# mother_card_13.net
KiCad netlist of a schematic drawn in EAGLE
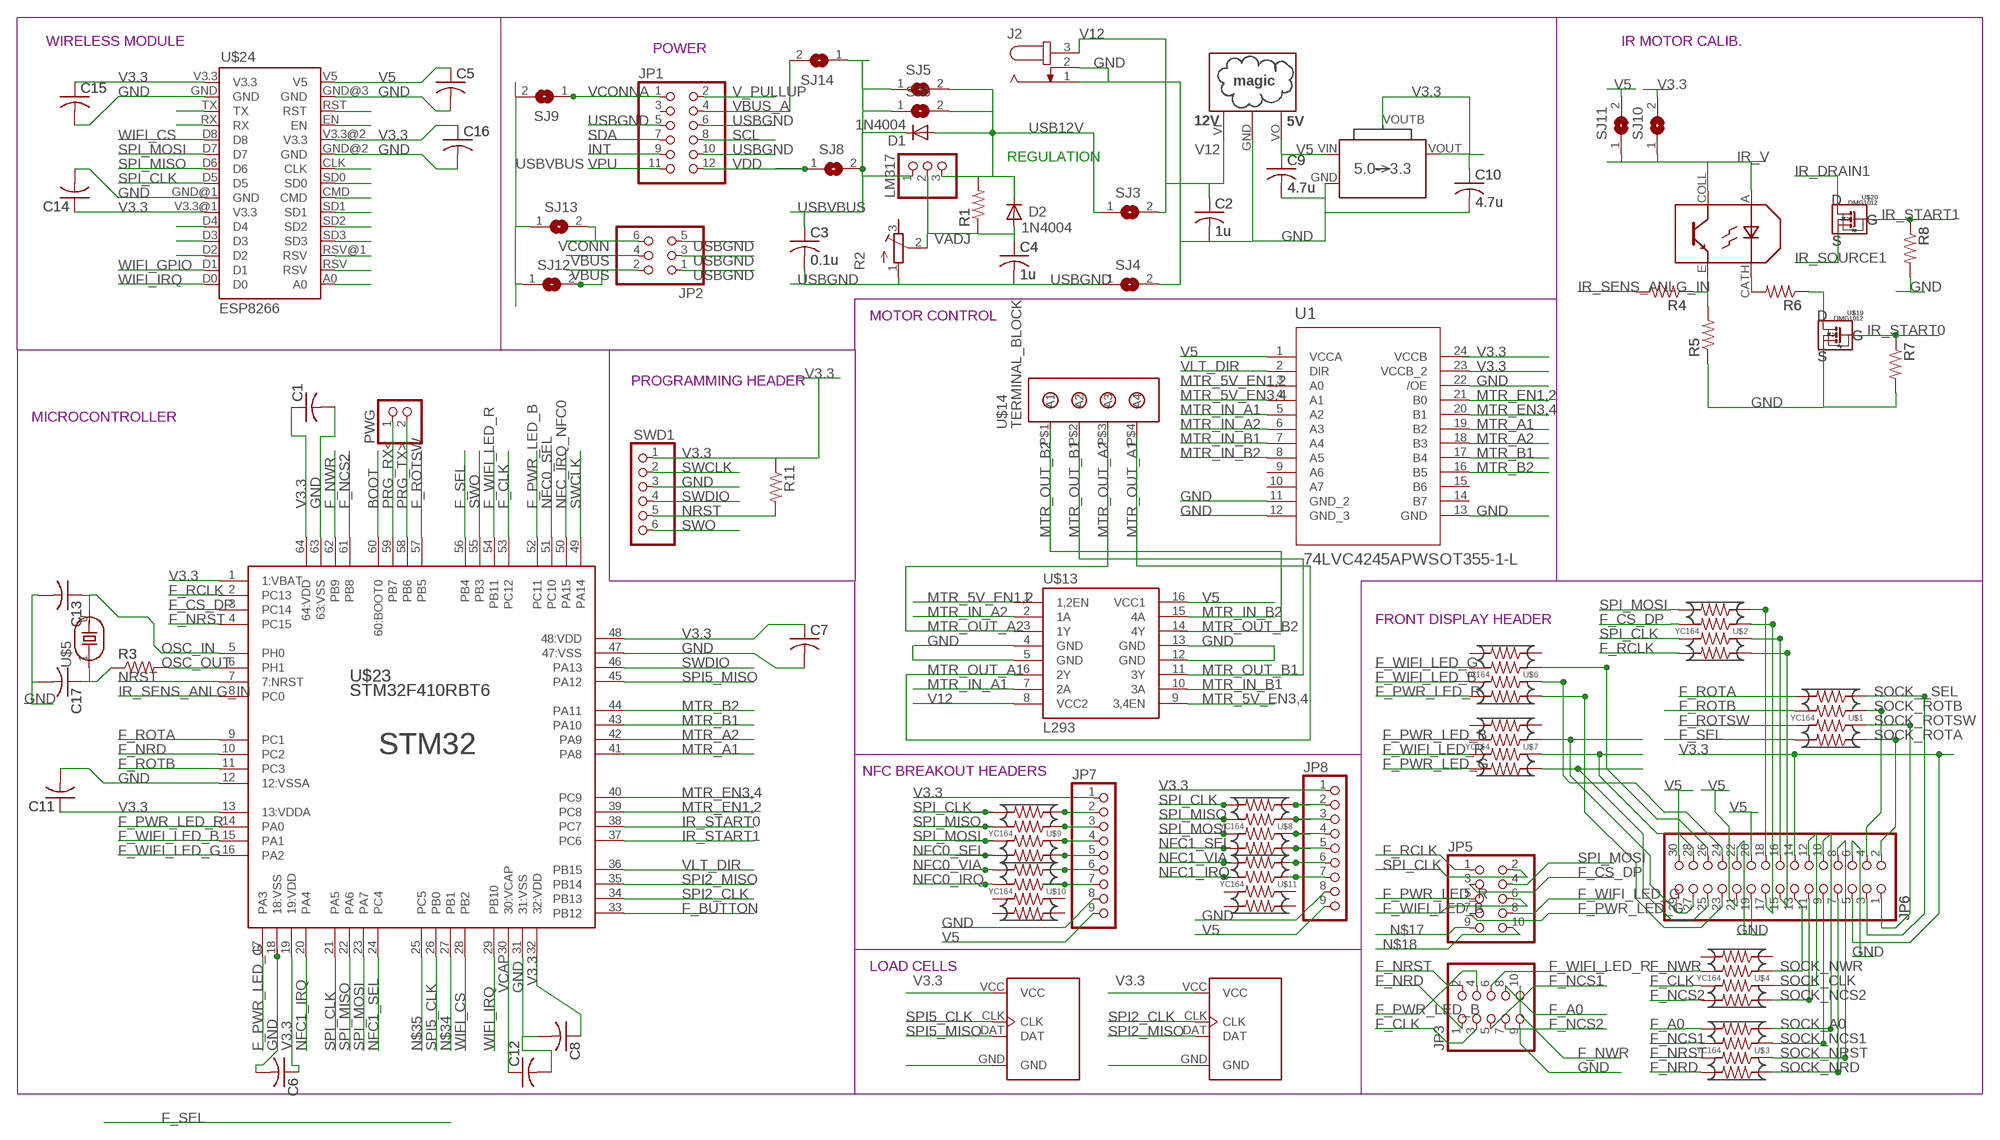
[diagram p0: schematic, sheet 1]

(export (version "E")
  (design (tool "Eeschema 10.0.6"))
  (components
    (comp (ref "C1")
      (value "C-USC0805")
      (footprint "eagle-import:C0805")
      (libsource (lib "eagle-import") (part "C-USC0805"))
    )
    (comp (ref "C2")
      (value "1u")
      (footprint "eagle-import:C0805")
      (libsource (lib "eagle-import") (part "C-USC0805"))
    )
    (comp (ref "C3")
      (value "0.1u")
      (footprint "eagle-import:C0805")
      (libsource (lib "eagle-import") (part "C-USC0805"))
    )
    (comp (ref "C4")
      (value "1u")
      (footprint "eagle-import:C0805")
      (libsource (lib "eagle-import") (part "C-USC0805"))
    )
    (comp (ref "C5")
      (value "C-USC0805")
      (footprint "eagle-import:C0805")
      (libsource (lib "eagle-import") (part "C-USC0805"))
    )
    (comp (ref "C6")
      (value "C-USC0805")
      (footprint "eagle-import:C0805")
      (libsource (lib "eagle-import") (part "C-USC0805"))
    )
    (comp (ref "C7")
      (value "C-USC0805")
      (footprint "eagle-import:C0805")
      (libsource (lib "eagle-import") (part "C-USC0805"))
    )
    (comp (ref "C8")
      (value "C-USC0805")
      (footprint "eagle-import:C0805")
      (libsource (lib "eagle-import") (part "C-USC0805"))
    )
    (comp (ref "C9")
      (value "4.7u")
      (footprint "eagle-import:C0805")
      (libsource (lib "eagle-import") (part "C-USC0805"))
    )
    (comp (ref "C10")
      (value "4.7u")
      (footprint "eagle-import:C0805")
      (libsource (lib "eagle-import") (part "C-USC0805"))
    )
    (comp (ref "C11")
      (value "C-USC0805")
      (footprint "eagle-import:C0805")
      (libsource (lib "eagle-import") (part "C-USC0805"))
    )
    (comp (ref "C12")
      (value "C-USC0805")
      (footprint "eagle-import:C0805")
      (libsource (lib "eagle-import") (part "C-USC0805"))
    )
    (comp (ref "C13")
      (value "C-USC0603")
      (footprint "eagle-import:C0603")
      (libsource (lib "eagle-import") (part "C-USC0603"))
    )
    (comp (ref "C14")
      (value "C-USC0805")
      (footprint "eagle-import:C0805")
      (libsource (lib "eagle-import") (part "C-USC0805"))
    )
    (comp (ref "C15")
      (value "C-USC0805")
      (footprint "eagle-import:C0805")
      (libsource (lib "eagle-import") (part "C-USC0805"))
    )
    (comp (ref "C16")
      (value "C-USC0805")
      (footprint "eagle-import:C0805")
      (libsource (lib "eagle-import") (part "C-USC0805"))
    )
    (comp (ref "C17")
      (value "C-USC0603")
      (footprint "eagle-import:C0603")
      (libsource (lib "eagle-import") (part "C-USC0603"))
    )
    (comp (ref "D1")
      (value "1N4004")
      (footprint "eagle-import:DO41-10")
      (libsource (lib "eagle-import") (part "1N4004"))
    )
    (comp (ref "D2")
      (value "1N4004")
      (footprint "eagle-import:DO41-10")
      (libsource (lib "eagle-import") (part "1N4004"))
    )
    (comp (ref "J2")
      (value "JACK-PLUG0")
      (footprint "eagle-import:SPC4077")
      (libsource (lib "eagle-import") (part "JACK-PLUG0"))
    )
    (comp (ref "JP1")
      (value "PINHD-2X6")
      (footprint "eagle-import:2X06")
      (libsource (lib "eagle-import") (part "PINHD-2X6"))
    )
    (comp (ref "JP2")
      (value "PINHD-2X3")
      (footprint "eagle-import:2X03")
      (libsource (lib "eagle-import") (part "PINHD-2X3"))
    )
    (comp (ref "JP3")
      (value "PINHD-2X5")
      (footprint "eagle-import:2X05")
      (libsource (lib "eagle-import") (part "PINHD-2X5"))
    )
    (comp (ref "JP5")
      (value "PINHD-2X5")
      (footprint "eagle-import:2X05")
      (libsource (lib "eagle-import") (part "PINHD-2X5"))
    )
    (comp (ref "JP6")
      (value "PINHD-2X15/SOCK")
      (footprint "eagle-import:2X15_SOCK")
      (libsource (lib "eagle-import") (part "PINHD-2X15/SOCK"))
    )
    (comp (ref "JP7")
      (value "PINHD-1X9/90")
      (footprint "eagle-import:1X09_90")
      (libsource (lib "eagle-import") (part "PINHD-1X9/90"))
    )
    (comp (ref "JP8")
      (value "PINHD-1X9/90")
      (footprint "eagle-import:1X09_90")
      (libsource (lib "eagle-import") (part "PINHD-1X9/90"))
    )
    (comp (ref "LM317")
      (value "PINHD-1X3")
      (footprint "eagle-import:1X03")
      (libsource (lib "eagle-import") (part "PINHD-1X3"))
    )
    (comp (ref "PWG")
      (value "PINHD-1X2")
      (footprint "eagle-import:1X02")
      (libsource (lib "eagle-import") (part "PINHD-1X2"))
    )
    (comp (ref "R1")
      (value "R-US_R0805")
      (footprint "eagle-import:R0805")
      (libsource (lib "eagle-import") (part "seniorDesign_R-US_R0805"))
    )
    (comp (ref "R2")
      (value "R-TRIMM64W")
      (footprint "eagle-import:RTRIM64W")
      (libsource (lib "eagle-import") (part "R-TRIMM64W"))
    )
    (comp (ref "R3")
      (value "R-US_R0805")
      (footprint "eagle-import:R0805")
      (libsource (lib "eagle-import") (part "seniorDesign_R-US_R0805"))
    )
    (comp (ref "R4")
      (value "R-US_R0805")
      (footprint "eagle-import:R0805")
      (libsource (lib "eagle-import") (part "seniorDesign_R-US_R0805"))
    )
    (comp (ref "R5")
      (value "R-US_R0805")
      (footprint "eagle-import:R0805")
      (libsource (lib "eagle-import") (part "seniorDesign_R-US_R0805"))
    )
    (comp (ref "R6")
      (value "R-US_R0805")
      (footprint "eagle-import:R0805")
      (libsource (lib "eagle-import") (part "seniorDesign_R-US_R0805"))
    )
    (comp (ref "R7")
      (value "R-US_R0805")
      (footprint "eagle-import:R0805")
      (libsource (lib "eagle-import") (part "seniorDesign_R-US_R0805"))
    )
    (comp (ref "R8")
      (value "R-US_R0805")
      (footprint "eagle-import:R0805")
      (libsource (lib "eagle-import") (part "seniorDesign_R-US_R0805"))
    )
    (comp (ref "R11")
      (value "R-US_R0805")
      (footprint "eagle-import:R0805")
      (libsource (lib "eagle-import") (part "R-US_R0805"))
    )
    (comp (ref "SJ3") (value "SJ") (footprint "eagle-import:SJ") (libsource (lib "eagle-import") (part "SJ")))
    (comp (ref "SJ4") (value "SJ") (footprint "eagle-import:SJ") (libsource (lib "eagle-import") (part "SJ")))
    (comp (ref "SJ5") (value "SJ") (footprint "eagle-import:SJ") (libsource (lib "eagle-import") (part "SJ")))
    (comp (ref "SJ6") (value "SJ") (footprint "eagle-import:SJ") (libsource (lib "eagle-import") (part "SJ")))
    (comp (ref "SJ8") (value "SJ") (footprint "eagle-import:SJ") (libsource (lib "eagle-import") (part "SJ")))
    (comp (ref "SJ9") (value "SJ") (footprint "eagle-import:SJ") (libsource (lib "eagle-import") (part "SJ")))
    (comp (ref "SJ10")
      (value "SJ")
      (footprint "eagle-import:SJ")
      (libsource (lib "eagle-import") (part "SJ"))
    )
    (comp (ref "SJ11")
      (value "SJ")
      (footprint "eagle-import:SJ")
      (libsource (lib "eagle-import") (part "SJ"))
    )
    (comp (ref "SJ12")
      (value "SJ")
      (footprint "eagle-import:SJ")
      (libsource (lib "eagle-import") (part "SJ"))
    )
    (comp (ref "SJ13")
      (value "SJ")
      (footprint "eagle-import:SJ")
      (libsource (lib "eagle-import") (part "SJ"))
    )
    (comp (ref "SJ14")
      (value "SJ")
      (footprint "eagle-import:SJ")
      (libsource (lib "eagle-import") (part "SJ"))
    )
    (comp (ref "SWD1")
      (value "PINHD-1X6")
      (footprint "eagle-import:1X06")
      (libsource (lib "eagle-import") (part "PINHD-1X6"))
    )
    (comp (ref "U$1")
      (value "YC164")
      (footprint "eagle-import:YC164")
      (libsource (lib "eagle-import") (part "YC164"))
    )
    (comp (ref "U$2")
      (value "YC164")
      (footprint "eagle-import:YC164")
      (libsource (lib "eagle-import") (part "YC164"))
    )
    (comp (ref "U$3")
      (value "YC164")
      (footprint "eagle-import:YC164")
      (libsource (lib "eagle-import") (part "YC164"))
    )
    (comp (ref "U$4")
      (value "YC164")
      (footprint "eagle-import:YC164")
      (libsource (lib "eagle-import") (part "YC164"))
    )
    (comp (ref "U$5")
      (value "HC-49S_9B")
      (footprint "eagle-import:HC-49S_9B")
      (libsource (lib "eagle-import") (part "HC-49S_9B"))
    )
    (comp (ref "U$6")
      (value "YC164")
      (footprint "eagle-import:YC164")
      (libsource (lib "eagle-import") (part "YC164"))
    )
    (comp (ref "U$7")
      (value "YC164")
      (footprint "eagle-import:YC164")
      (libsource (lib "eagle-import") (part "YC164"))
    )
    (comp (ref "U$8")
      (value "YC164")
      (footprint "eagle-import:YC164")
      (libsource (lib "eagle-import") (part "YC164"))
    )
    (comp (ref "U$9")
      (value "YC164")
      (footprint "eagle-import:YC164")
      (libsource (lib "eagle-import") (part "YC164"))
    )
    (comp (ref "U$10")
      (value "YC164")
      (footprint "eagle-import:YC164")
      (libsource (lib "eagle-import") (part "YC164"))
    )
    (comp (ref "U$11")
      (value "YC164")
      (footprint "eagle-import:YC164")
      (libsource (lib "eagle-import") (part "YC164"))
    )
    (comp (ref "U$13")
      (value "L293")
      (footprint "eagle-import:DIL16")
      (libsource (lib "eagle-import") (part "L293"))
    )
    (comp (ref "U$14")
      (value "TERMINAL_BLOCK")
      (footprint "eagle-import:1X4_BLOCK")
      (libsource (lib "eagle-import") (part "TERMINAL_BLOCK"))
    )
    (comp (ref "U$15")
      (value "AP2114H")
      (footprint "eagle-import:AP2114H")
      (libsource (lib "eagle-import") (part "AP2114H"))
    )
    (comp (ref "U$16")
      (value "OKI-78SR-W36")
      (footprint "eagle-import:SIP3")
      (libsource (lib "eagle-import") (part "OKI-78SR-W36"))
    )
    (comp (ref "U$18")
      (value "TCRT5000")
      (footprint "eagle-import:TCRT5000")
      (libsource (lib "eagle-import") (part "TCRT5000"))
    )
    (comp (ref "U$19")
      (value "DMG1012")
      (footprint "eagle-import:SOT323")
      (libsource (lib "eagle-import") (part "DMG1012"))
    )
    (comp (ref "U$20")
      (value "DMG1012")
      (footprint "eagle-import:SOT323")
      (libsource (lib "eagle-import") (part "DMG1012"))
    )
    (comp (ref "U$21")
      (value "HX711")
      (footprint "eagle-import:HX711")
      (libsource (lib "eagle-import") (part "HX711"))
    )
    (comp (ref "U$22")
      (value "HX711")
      (footprint "eagle-import:HX711")
      (libsource (lib "eagle-import") (part "HX711"))
    )
    (comp (ref "U$23")
      (value "STM32F410RBT6")
      (footprint "eagle-import:QFP50P1200X1200X160-64N")
      (libsource (lib "eagle-import") (part "STM32F410RBT6"))
    )
    (comp (ref "U$24")
      (value "ESP8266")
      (footprint "eagle-import:ESP8266")
      (libsource (lib "eagle-import") (part "ESP8266"))
    )
    (comp (ref "U1")
      (value "74LVC4245APWSOT355-1-L")
      (footprint "eagle-import:SOT355-1-L")
      (fields (field (name "MANUFACTURER_PART_NUMBER") "74LVC4245APW"))
      (libsource (lib "eagle-import") (part "74LVC4245APWSOT355-1-L"))
    )
  )
  (nets
    (net (code "1") (name "/BOOT") (class "Default")
      (node (ref "U$23") (pin "60") (pinfunction "60:BOOT0_60") (pintype "bidirectional"))
    )
    (net (code "2") (name "/F_A0") (class "Default")
      (node (ref "JP3") (pin "8") (pinfunction "8_8") (pintype "passive"))
      (node (ref "U$3") (pin "P$4") (pinfunction "4_P$4") (pintype "passive"))
    )
    (net (code "3") (name "/F_BUTTON") (class "Default")
      (node (ref "U$23") (pin "33") (pinfunction "PB12_33") (pintype "bidirectional"))
    )
    (net (code "4") (name "/F_CLK") (class "Default")
      (node (ref "JP3") (pin "3") (pinfunction "3_3") (pintype "passive"))
      (node (ref "U$23") (pin "53") (pinfunction "PC12_53") (pintype "bidirectional"))
      (node (ref "U$4") (pin "P$2") (pinfunction "2_P$2") (pintype "passive"))
    )
    (net (code "5") (name "/F_CS_DP") (class "Default")
      (node (ref "JP5") (pin "3") (pinfunction "3_3") (pintype "passive"))
      (node (ref "U$2") (pin "P$3") (pinfunction "3_P$3") (pintype "passive"))
      (node (ref "U$23") (pin "3") (pinfunction "PC14_3") (pintype "bidirectional"))
    )
    (net (code "6") (name "/F_NCS1") (class "Default")
      (node (ref "JP3") (pin "5") (pinfunction "5_5") (pintype "passive"))
      (node (ref "U$3") (pin "P$3") (pinfunction "3_P$3") (pintype "passive"))
    )
    (net (code "7") (name "/F_NCS2") (class "Default")
      (node (ref "JP3") (pin "7") (pinfunction "7_7") (pintype "passive"))
      (node (ref "U$23") (pin "61") (pinfunction "PB8_61") (pintype "bidirectional"))
      (node (ref "U$4") (pin "P$1") (pinfunction "1_P$1") (pintype "passive"))
    )
    (net (code "8") (name "/F_NRD") (class "Default")
      (node (ref "JP3") (pin "1") (pinfunction "1_1") (pintype "passive"))
      (node (ref "U$23") (pin "10") (pinfunction "PC2_10") (pintype "bidirectional"))
      (node (ref "U$3") (pin "P$1") (pinfunction "1_P$1") (pintype "passive"))
    )
    (net (code "9") (name "/F_NRST") (class "Default")
      (node (ref "JP3") (pin "2") (pinfunction "2_2") (pintype "passive"))
      (node (ref "U$23") (pin "4") (pinfunction "PC15_4") (pintype "bidirectional"))
      (node (ref "U$3") (pin "P$2") (pinfunction "2_P$2") (pintype "passive"))
    )
    (net (code "10") (name "/F_NWR") (class "Default")
      (node (ref "JP3") (pin "10") (pinfunction "10_10") (pintype "passive"))
      (node (ref "U$23") (pin "62") (pinfunction "PB9_62") (pintype "bidirectional"))
      (node (ref "U$4") (pin "P$3") (pinfunction "3_P$3") (pintype "passive"))
    )
    (net (code "11") (name "/F_PWR_LED_B") (class "Default")
      (node (ref "JP3") (pin "4") (pinfunction "4_4") (pintype "passive"))
      (node (ref "U$23") (pin "52") (pinfunction "PC11_52") (pintype "bidirectional"))
      (node (ref "U$7") (pin "P$3") (pinfunction "3_P$3") (pintype "passive"))
    )
    (net (code "12") (name "/F_PWR_LED_G") (class "Default")
      (node (ref "JP5") (pin "7") (pinfunction "7_7") (pintype "passive"))
      (node (ref "U$23") (pin "17") (pinfunction "PA3_17") (pintype "bidirectional"))
      (node (ref "U$7") (pin "P$1") (pinfunction "1_P$1") (pintype "passive"))
    )
    (net (code "13") (name "/F_PWR_LED_R") (class "Default")
      (node (ref "JP5") (pin "5") (pinfunction "5_5") (pintype "passive"))
      (node (ref "U$23") (pin "14") (pinfunction "PA0_14") (pintype "bidirectional"))
      (node (ref "U$6") (pin "P$1") (pinfunction "1_P$1") (pintype "passive"))
    )
    (net (code "14") (name "/F_RCLK") (class "Default")
      (node (ref "JP5") (pin "1") (pinfunction "1_1") (pintype "passive"))
      (node (ref "U$2") (pin "P$1") (pinfunction "1_P$1") (pintype "passive"))
      (node (ref "U$23") (pin "2") (pinfunction "PC13_2") (pintype "bidirectional"))
    )
    (net (code "15") (name "/F_ROTA") (class "Default")
      (node (ref "U$1") (pin "P$4") (pinfunction "4_P$4") (pintype "passive"))
      (node (ref "U$23") (pin "9") (pinfunction "PC1_9") (pintype "bidirectional"))
    )
    (net (code "16") (name "/F_ROTB") (class "Default")
      (node (ref "U$1") (pin "P$3") (pinfunction "3_P$3") (pintype "passive"))
      (node (ref "U$23") (pin "11") (pinfunction "PC3_11") (pintype "bidirectional"))
    )
    (net (code "17") (name "/F_ROTSW") (class "Default")
      (node (ref "U$1") (pin "P$2") (pinfunction "2_P$2") (pintype "passive"))
      (node (ref "U$23") (pin "57") (pinfunction "PB5_57") (pintype "bidirectional"))
    )
    (net (code "18") (name "/F_SEL") (class "Default")
      (node (ref "U$1") (pin "P$1") (pinfunction "1_P$1") (pintype "passive"))
      (node (ref "U$23") (pin "56") (pinfunction "PB4_56") (pintype "bidirectional"))
    )
    (net (code "19") (name "/F_WIFI_LED_B") (class "Default")
      (node (ref "JP5") (pin "6") (pinfunction "6_6") (pintype "passive"))
      (node (ref "U$23") (pin "15") (pinfunction "PA1_15") (pintype "bidirectional"))
      (node (ref "U$6") (pin "P$2") (pinfunction "2_P$2") (pintype "passive"))
    )
    (net (code "20") (name "/F_WIFI_LED_G") (class "Default")
      (node (ref "JP5") (pin "8") (pinfunction "8_8") (pintype "passive"))
      (node (ref "U$23") (pin "16") (pinfunction "PA2_16") (pintype "bidirectional"))
      (node (ref "U$6") (pin "P$3") (pinfunction "3_P$3") (pintype "passive"))
    )
    (net (code "21") (name "/F_WIFI_LED_R") (class "Default")
      (node (ref "JP3") (pin "6") (pinfunction "6_6") (pintype "passive"))
      (node (ref "U$23") (pin "54") (pinfunction "PB11_54") (pintype "bidirectional"))
      (node (ref "U$7") (pin "P$2") (pinfunction "2_P$2") (pintype "passive"))
    )
    (net (code "22") (name "/GND") (class "Default")
      (node (ref "C1") (pin "2") (pinfunction "2_2") (pintype "passive"))
      (node (ref "C10") (pin "2") (pinfunction "2_2") (pintype "passive"))
      (node (ref "C11") (pin "2") (pinfunction "2_2") (pintype "passive"))
      (node (ref "C12") (pin "2") (pinfunction "2_2") (pintype "passive"))
      (node (ref "C13") (pin "2") (pinfunction "2_2") (pintype "passive"))
      (node (ref "C14") (pin "2") (pinfunction "2_2") (pintype "passive"))
      (node (ref "C15") (pin "2") (pinfunction "2_2") (pintype "passive"))
      (node (ref "C16") (pin "2") (pinfunction "2_2") (pintype "passive"))
      (node (ref "C17") (pin "2") (pinfunction "2_2") (pintype "passive"))
      (node (ref "C2") (pin "2") (pinfunction "2_2") (pintype "passive"))
      (node (ref "C5") (pin "2") (pinfunction "2_2") (pintype "passive"))
      (node (ref "C6") (pin "2") (pinfunction "2_2") (pintype "passive"))
      (node (ref "C7") (pin "2") (pinfunction "2_2") (pintype "passive"))
      (node (ref "C8") (pin "2") (pinfunction "2_2") (pintype "passive"))
      (node (ref "C9") (pin "2") (pinfunction "2_2") (pintype "passive"))
      (node (ref "J2") (pin "1") (pinfunction "1_1") (pintype "passive"))
      (node (ref "J2") (pin "2") (pinfunction "2_2") (pintype "passive"))
      (node (ref "JP3") (pin "9") (pinfunction "9_9") (pintype "passive"))
      (node (ref "JP6") (pin "19") (pinfunction "19_19") (pintype "passive"))
      (node (ref "JP6") (pin "22") (pinfunction "22_22") (pintype "passive"))
      (node (ref "JP6") (pin "6") (pinfunction "6_6") (pintype "passive"))
      (node (ref "JP7") (pin "8") (pinfunction "8_8") (pintype "passive"))
      (node (ref "JP8") (pin "8") (pinfunction "8_8") (pintype "passive"))
      (node (ref "R5") (pin "1") (pinfunction "1_1") (pintype "passive"))
      (node (ref "R7") (pin "2") (pinfunction "2_2") (pintype "passive"))
      (node (ref "R8") (pin "2") (pinfunction "2_2") (pintype "passive"))
      (node (ref "SJ4") (pin "2") (pinfunction "2_2") (pintype "passive"))
      (node (ref "SWD1") (pin "3") (pinfunction "3_3") (pintype "passive"))
      (node (ref "U$13") (pin "12") (pinfunction "GND_12") (pintype "bidirectional"))
      (node (ref "U$13") (pin "13") (pinfunction "GND_13") (pintype "bidirectional"))
      (node (ref "U$13") (pin "4") (pinfunction "GND_4") (pintype "bidirectional"))
      (node (ref "U$13") (pin "5") (pinfunction "GND_5") (pintype "bidirectional"))
      (node (ref "U$15") (pin "GND") (pinfunction "GND_GND") (pintype "power_in"))
      (node (ref "U$16") (pin "GND") (pinfunction "P$2_GND") (pintype "power_in"))
      (node (ref "U$19") (pin "S") (pinfunction "S_S") (pintype "bidirectional"))
      (node (ref "U$21") (pin "GND") (pinfunction "GND_GND") (pintype "power_in"))
      (node (ref "U$22") (pin "GND") (pinfunction "GND_GND") (pintype "power_in"))
      (node (ref "U$23") (pin "12") (pinfunction "12:VSSA_12") (pintype "bidirectional"))
      (node (ref "U$23") (pin "18") (pinfunction "18:VSS_18") (pintype "bidirectional"))
      (node (ref "U$23") (pin "31") (pinfunction "31:VSS_31") (pintype "bidirectional"))
      (node (ref "U$23") (pin "47") (pinfunction "47:VSS_47") (pintype "bidirectional"))
      (node (ref "U$23") (pin "63") (pinfunction "63:VSS_63") (pintype "bidirectional"))
      (node (ref "U$24") (pin "GND") (pinfunction "GND_GND") (pintype "bidirectional"))
      (node (ref "U$24") (pin "GND@1") (pinfunction "GND_GND@1") (pintype "bidirectional"))
      (node (ref "U$24") (pin "GND@2") (pinfunction "GND_GND@2") (pintype "bidirectional"))
      (node (ref "U$24") (pin "GND@3") (pinfunction "GND_GND@3") (pintype "bidirectional"))
      (node (ref "U1") (pin "11") (pinfunction "GND_2_11") (pintype "power_in"))
      (node (ref "U1") (pin "12") (pinfunction "GND_3_12") (pintype "power_in"))
      (node (ref "U1") (pin "13") (pinfunction "GND_13") (pintype "power_in"))
      (node (ref "U1") (pin "22") (pinfunction "/OE_22") (pintype "input"))
    )
    (net (code "23") (name "/INT") (class "Default")
      (node (ref "JP1") (pin "9") (pinfunction "9_9") (pintype "passive"))
    )
    (net (code "24") (name "/IR_DRAIN1") (class "Default")
      (node (ref "U$20") (pin "D") (pinfunction "D_D") (pintype "bidirectional"))
    )
    (net (code "25") (name "/IR_SENS_ANLG_IN") (class "Default")
      (node (ref "R4") (pin "2") (pinfunction "2_2") (pintype "passive"))
      (node (ref "U$23") (pin "8") (pinfunction "PC0_8") (pintype "bidirectional"))
    )
    (net (code "26") (name "/IR_SOURCE1") (class "Default")
      (node (ref "U$20") (pin "S") (pinfunction "S_S") (pintype "bidirectional"))
    )
    (net (code "27") (name "/IR_START0") (class "Default")
      (node (ref "R7") (pin "1") (pinfunction "1_1") (pintype "passive"))
      (node (ref "U$19") (pin "G") (pinfunction "G_G") (pintype "bidirectional"))
      (node (ref "U$23") (pin "38") (pinfunction "PC7_38") (pintype "bidirectional"))
    )
    (net (code "28") (name "/IR_START1") (class "Default")
      (node (ref "R8") (pin "1") (pinfunction "1_1") (pintype "passive"))
      (node (ref "U$20") (pin "G") (pinfunction "G_G") (pintype "bidirectional"))
      (node (ref "U$23") (pin "37") (pinfunction "PC6_37") (pintype "bidirectional"))
    )
    (net (code "29") (name "/IR_V") (class "Default")
      (node (ref "SJ10") (pin "1") (pinfunction "1_1") (pintype "passive"))
      (node (ref "SJ11") (pin "1") (pinfunction "1_1") (pintype "passive"))
      (node (ref "U$18") (pin "A") (pinfunction "A_A") (pintype "bidirectional"))
      (node (ref "U$18") (pin "COLL") (pinfunction "COLL_COLL") (pintype "bidirectional"))
    )
    (net (code "30") (name "/MTR_5V_EN1,2") (class "Default")
      (node (ref "U$13") (pin "1") (pinfunction "1,2EN_1") (pintype "bidirectional"))
      (node (ref "U1") (pin "3") (pinfunction "A0_3") (pintype "bidirectional"))
    )
    (net (code "31") (name "/MTR_5V_EN3,4") (class "Default")
      (node (ref "U$13") (pin "9") (pinfunction "3,4EN_9") (pintype "bidirectional"))
      (node (ref "U1") (pin "4") (pinfunction "A1_4") (pintype "bidirectional"))
    )
    (net (code "32") (name "/MTR_A1") (class "Default")
      (node (ref "U$23") (pin "41") (pinfunction "PA8_41") (pintype "bidirectional"))
      (node (ref "U1") (pin "19") (pinfunction "B2_19") (pintype "bidirectional"))
    )
    (net (code "33") (name "/MTR_A2") (class "Default")
      (node (ref "U$23") (pin "42") (pinfunction "PA9_42") (pintype "bidirectional"))
      (node (ref "U1") (pin "18") (pinfunction "B3_18") (pintype "bidirectional"))
    )
    (net (code "34") (name "/MTR_B1") (class "Default")
      (node (ref "U$23") (pin "43") (pinfunction "PA10_43") (pintype "bidirectional"))
      (node (ref "U1") (pin "17") (pinfunction "B4_17") (pintype "bidirectional"))
    )
    (net (code "35") (name "/MTR_B2") (class "Default")
      (node (ref "U$23") (pin "44") (pinfunction "PA11_44") (pintype "bidirectional"))
      (node (ref "U1") (pin "16") (pinfunction "B5_16") (pintype "bidirectional"))
    )
    (net (code "36") (name "/MTR_EN1,2") (class "Default")
      (node (ref "U$23") (pin "39") (pinfunction "PC8_39") (pintype "bidirectional"))
      (node (ref "U1") (pin "21") (pinfunction "B0_21") (pintype "bidirectional"))
    )
    (net (code "37") (name "/MTR_EN3,4") (class "Default")
      (node (ref "U$23") (pin "40") (pinfunction "PC9_40") (pintype "bidirectional"))
      (node (ref "U1") (pin "20") (pinfunction "B1_20") (pintype "bidirectional"))
    )
    (net (code "38") (name "/MTR_IN_A1") (class "Default")
      (node (ref "U$13") (pin "7") (pinfunction "2A_7") (pintype "bidirectional"))
      (node (ref "U1") (pin "5") (pinfunction "A2_5") (pintype "bidirectional"))
    )
    (net (code "39") (name "/MTR_IN_A2") (class "Default")
      (node (ref "U$13") (pin "2") (pinfunction "1A_2") (pintype "bidirectional"))
      (node (ref "U1") (pin "6") (pinfunction "A3_6") (pintype "bidirectional"))
    )
    (net (code "40") (name "/MTR_IN_B1") (class "Default")
      (node (ref "U$13") (pin "10") (pinfunction "3A_10") (pintype "bidirectional"))
      (node (ref "U1") (pin "7") (pinfunction "A4_7") (pintype "bidirectional"))
    )
    (net (code "41") (name "/MTR_IN_B2") (class "Default")
      (node (ref "U$13") (pin "15") (pinfunction "4A_15") (pintype "bidirectional"))
      (node (ref "U1") (pin "8") (pinfunction "A5_8") (pintype "bidirectional"))
    )
    (net (code "42") (name "/MTR_OUT_A1") (class "Default")
      (node (ref "U$13") (pin "6") (pinfunction "2Y_6") (pintype "bidirectional"))
      (node (ref "U$14") (pin "P$4") (pinfunction "A4_P$4") (pintype "bidirectional"))
    )
    (net (code "43") (name "/MTR_OUT_A2") (class "Default")
      (node (ref "U$13") (pin "3") (pinfunction "1Y_3") (pintype "bidirectional"))
      (node (ref "U$14") (pin "P$3") (pinfunction "A3_P$3") (pintype "bidirectional"))
    )
    (net (code "44") (name "/MTR_OUT_B1") (class "Default")
      (node (ref "U$13") (pin "11") (pinfunction "3Y_11") (pintype "bidirectional"))
      (node (ref "U$14") (pin "P$2") (pinfunction "A2_P$2") (pintype "bidirectional"))
    )
    (net (code "45") (name "/MTR_OUT_B2") (class "Default")
      (node (ref "U$13") (pin "14") (pinfunction "4Y_14") (pintype "bidirectional"))
      (node (ref "U$14") (pin "P$1") (pinfunction "A1_P$1") (pintype "bidirectional"))
    )
    (net (code "46") (name "/N$17") (class "Default")
      (node (ref "JP5") (pin "9") (pinfunction "9_9") (pintype "passive"))
    )
    (net (code "47") (name "/N$18") (class "Default")
      (node (ref "JP5") (pin "10") (pinfunction "10_10") (pintype "passive"))
    )
    (net (code "48") (name "/N$34") (class "Default")
      (node (ref "U$23") (pin "27") (pinfunction "PB1_27") (pintype "bidirectional"))
    )
    (net (code "49") (name "/N$35") (class "Default")
      (node (ref "U$23") (pin "25") (pinfunction "PC5_25") (pintype "bidirectional"))
    )
    (net (code "50") (name "/NFC0_IRQ") (class "Default")
      (node (ref "U$10") (pin "P$3") (pinfunction "3_P$3") (pintype "passive"))
    )
    (net (code "51") (name "/NFC0_SEL") (class "Default")
      (node (ref "U$23") (pin "51") (pinfunction "PC10_51") (pintype "bidirectional"))
      (node (ref "U$9") (pin "P$1") (pinfunction "1_P$1") (pintype "passive"))
    )
    (net (code "52") (name "/NFC0_VIA") (class "Default")
      (node (ref "U$10") (pin "P$4") (pinfunction "4_P$4") (pintype "passive"))
    )
    (net (code "53") (name "/NFC1_IRQ") (class "Default")
      (node (ref "U$11") (pin "P$3") (pinfunction "3_P$3") (pintype "passive"))
      (node (ref "U$23") (pin "20") (pinfunction "PA4_20") (pintype "bidirectional"))
    )
    (net (code "54") (name "/NFC1_SEL") (class "Default")
      (node (ref "U$23") (pin "24") (pinfunction "PC4_24") (pintype "bidirectional"))
      (node (ref "U$8") (pin "P$1") (pinfunction "1_P$1") (pintype "passive"))
    )
    (net (code "55") (name "/NFC1_VIA") (class "Default")
      (node (ref "U$11") (pin "P$4") (pinfunction "4_P$4") (pintype "passive"))
    )
    (net (code "56") (name "/NFC_IRQ_NFC0") (class "Default")
      (node (ref "U$23") (pin "50") (pinfunction "PA15_50") (pintype "bidirectional"))
    )
    (net (code "57") (name "/NRST") (class "Default")
      (node (ref "R11") (pin "2") (pinfunction "2_2") (pintype "passive"))
      (node (ref "SWD1") (pin "5") (pinfunction "5_5") (pintype "passive"))
      (node (ref "U$23") (pin "7") (pinfunction "7:NRST_7") (pintype "bidirectional"))
    )
    (net (code "58") (name "/OSC_IN") (class "Default")
      (node (ref "C13") (pin "1") (pinfunction "1_1") (pintype "passive"))
      (node (ref "U$23") (pin "5") (pinfunction "PH0_5") (pintype "bidirectional"))
      (node (ref "U$5") (pin "0") (pinfunction "P$1_0") (pintype "bidirectional"))
    )
    (net (code "59") (name "/OSC_OUT") (class "Default")
      (node (ref "C17") (pin "1") (pinfunction "1_1") (pintype "passive"))
      (node (ref "R3") (pin "1") (pinfunction "1_1") (pintype "passive"))
      (node (ref "U$5") (pin "1") (pinfunction "P$2_1") (pintype "bidirectional"))
    )
    (net (code "60") (name "/PRG_RX<") (class "Default")
      (node (ref "PWG") (pin "1") (pinfunction "1_1") (pintype "passive"))
      (node (ref "U$23") (pin "59") (pinfunction "PB7_59") (pintype "bidirectional"))
    )
    (net (code "61") (name "/PRG_TX>") (class "Default")
      (node (ref "PWG") (pin "2") (pinfunction "2_2") (pintype "passive"))
      (node (ref "U$23") (pin "58") (pinfunction "PB6_58") (pintype "bidirectional"))
    )
    (net (code "62") (name "/SCL") (class "Default")
      (node (ref "JP1") (pin "8") (pinfunction "8_8") (pintype "passive"))
    )
    (net (code "63") (name "/SDA") (class "Default")
      (node (ref "JP1") (pin "7") (pinfunction "7_7") (pintype "passive"))
    )
    (net (code "64") (name "/SOCK_A0") (class "Default")
      (node (ref "JP6") (pin "10") (pinfunction "10_10") (pintype "passive"))
      (node (ref "U$3") (pin "P$44") (pinfunction "44_P$44") (pintype "passive"))
    )
    (net (code "65") (name "/SOCK_CLK") (class "Default")
      (node (ref "JP6") (pin "12") (pinfunction "12_12") (pintype "passive"))
      (node (ref "U$4") (pin "P$22") (pinfunction "22_P$22") (pintype "passive"))
    )
    (net (code "66") (name "/SOCK_NCS1") (class "Default")
      (node (ref "JP6") (pin "9") (pinfunction "9_9") (pintype "passive"))
      (node (ref "U$3") (pin "P$33") (pinfunction "33_P$33") (pintype "passive"))
    )
    (net (code "67") (name "/SOCK_NCS2") (class "Default")
      (node (ref "JP6") (pin "11") (pinfunction "11_11") (pintype "passive"))
      (node (ref "U$4") (pin "P$11") (pinfunction "11_P$11") (pintype "passive"))
    )
    (net (code "68") (name "/SOCK_NRD") (class "Default")
      (node (ref "JP6") (pin "7") (pinfunction "7_7") (pintype "passive"))
      (node (ref "U$3") (pin "P$11") (pinfunction "11_P$11") (pintype "passive"))
    )
    (net (code "69") (name "/SOCK_NRST") (class "Default")
      (node (ref "JP6") (pin "8") (pinfunction "8_8") (pintype "passive"))
      (node (ref "U$3") (pin "P$22") (pinfunction "22_P$22") (pintype "passive"))
    )
    (net (code "70") (name "/SOCK_NWR") (class "Default")
      (node (ref "JP6") (pin "13") (pinfunction "13_13") (pintype "passive"))
      (node (ref "U$4") (pin "P$33") (pinfunction "33_P$33") (pintype "passive"))
    )
    (net (code "71") (name "/SOCK_ROTA") (class "Default")
      (node (ref "JP6") (pin "2") (pinfunction "2_2") (pintype "passive"))
      (node (ref "U$1") (pin "P$11") (pinfunction "11_P$11") (pintype "passive"))
    )
    (net (code "72") (name "/SOCK_ROTB") (class "Default")
      (node (ref "JP6") (pin "4") (pinfunction "4_4") (pintype "passive"))
      (node (ref "U$1") (pin "P$33") (pinfunction "33_P$33") (pintype "passive"))
    )
    (net (code "73") (name "/SOCK_ROTSW") (class "Default")
      (node (ref "JP6") (pin "1") (pinfunction "1_1") (pintype "passive"))
      (node (ref "U$1") (pin "P$22") (pinfunction "22_P$22") (pintype "passive"))
    )
    (net (code "74") (name "/SOCK__SEL") (class "Default")
      (node (ref "JP6") (pin "3") (pinfunction "3_3") (pintype "passive"))
      (node (ref "U$1") (pin "P$44") (pinfunction "44_P$44") (pintype "passive"))
    )
    (net (code "75") (name "/SPI2_CLK") (class "Default")
      (node (ref "U$22") (pin "CLK") (pinfunction "CLK_CLK") (pintype "bidirectional"))
      (node (ref "U$23") (pin "34") (pinfunction "PB13_34") (pintype "bidirectional"))
    )
    (net (code "76") (name "/SPI2_MISO") (class "Default")
      (node (ref "U$22") (pin "DAT") (pinfunction "DAT_DAT") (pintype "bidirectional"))
      (node (ref "U$23") (pin "35") (pinfunction "PB14_35") (pintype "bidirectional"))
    )
    (net (code "77") (name "/SPI5_CLK") (class "Default")
      (node (ref "U$21") (pin "CLK") (pinfunction "CLK_CLK") (pintype "bidirectional"))
      (node (ref "U$23") (pin "26") (pinfunction "PB0_26") (pintype "bidirectional"))
    )
    (net (code "78") (name "/SPI5_MISO") (class "Default")
      (node (ref "U$21") (pin "DAT") (pinfunction "DAT_DAT") (pintype "bidirectional"))
      (node (ref "U$23") (pin "45") (pinfunction "PA12_45") (pintype "bidirectional"))
    )
    (net (code "79") (name "/SPI_CLK") (class "Default")
      (node (ref "JP5") (pin "2") (pinfunction "2_2") (pintype "passive"))
      (node (ref "U$2") (pin "P$2") (pinfunction "2_P$2") (pintype "passive"))
      (node (ref "U$23") (pin "21") (pinfunction "PA5_21") (pintype "bidirectional"))
      (node (ref "U$24") (pin "D5") (pinfunction "D5_D5") (pintype "bidirectional"))
      (node (ref "U$8") (pin "P$4") (pinfunction "4_P$4") (pintype "passive"))
      (node (ref "U$9") (pin "P$4") (pinfunction "4_P$4") (pintype "passive"))
    )
    (net (code "80") (name "/SPI_MISO") (class "Default")
      (node (ref "U$23") (pin "22") (pinfunction "PA6_22") (pintype "bidirectional"))
      (node (ref "U$24") (pin "D6") (pinfunction "D6_D6") (pintype "bidirectional"))
      (node (ref "U$8") (pin "P$3") (pinfunction "3_P$3") (pintype "passive"))
      (node (ref "U$9") (pin "P$3") (pinfunction "3_P$3") (pintype "passive"))
    )
    (net (code "81") (name "/SPI_MOSI") (class "Default")
      (node (ref "JP5") (pin "4") (pinfunction "4_4") (pintype "passive"))
      (node (ref "U$2") (pin "P$4") (pinfunction "4_P$4") (pintype "passive"))
      (node (ref "U$23") (pin "23") (pinfunction "PA7_23") (pintype "bidirectional"))
      (node (ref "U$24") (pin "D7") (pinfunction "D7_D7") (pintype "bidirectional"))
      (node (ref "U$8") (pin "P$2") (pinfunction "2_P$2") (pintype "passive"))
      (node (ref "U$9") (pin "P$2") (pinfunction "2_P$2") (pintype "passive"))
    )
    (net (code "82") (name "/SWCLK") (class "Default")
      (node (ref "SWD1") (pin "2") (pinfunction "2_2") (pintype "passive"))
      (node (ref "U$23") (pin "49") (pinfunction "PA14_49") (pintype "bidirectional"))
    )
    (net (code "83") (name "/SWDIO") (class "Default")
      (node (ref "SWD1") (pin "4") (pinfunction "4_4") (pintype "passive"))
      (node (ref "U$23") (pin "46") (pinfunction "PA13_46") (pintype "bidirectional"))
    )
    (net (code "84") (name "/SWO") (class "Default")
      (node (ref "SWD1") (pin "6") (pinfunction "6_6") (pintype "passive"))
      (node (ref "U$23") (pin "55") (pinfunction "PB3_55") (pintype "bidirectional"))
    )
    (net (code "85") (name "/USB12V") (class "Default")
      (node (ref "D1") (pin "A") (pinfunction "A_A") (pintype "passive"))
      (node (ref "D2") (pin "C") (pinfunction "C_C") (pintype "passive"))
      (node (ref "LM317") (pin "3") (pinfunction "3_3") (pintype "passive"))
      (node (ref "R1") (pin "2") (pinfunction "2_2") (pintype "passive"))
      (node (ref "SJ3") (pin "1") (pinfunction "1_1") (pintype "passive"))
      (node (ref "SJ5") (pin "2") (pinfunction "2_2") (pintype "passive"))
      (node (ref "SJ6") (pin "2") (pinfunction "2_2") (pintype "passive"))
    )
    (net (code "86") (name "/USBGND") (class "Default")
      (node (ref "C3") (pin "2") (pinfunction "2_2") (pintype "passive"))
      (node (ref "C4") (pin "2") (pinfunction "2_2") (pintype "passive"))
      (node (ref "JP1") (pin "10") (pinfunction "10_10") (pintype "passive"))
      (node (ref "JP1") (pin "5") (pinfunction "5_5") (pintype "passive"))
      (node (ref "JP1") (pin "6") (pinfunction "6_6") (pintype "passive"))
      (node (ref "JP2") (pin "1") (pinfunction "1_1") (pintype "passive"))
      (node (ref "JP2") (pin "3") (pinfunction "3_3") (pintype "passive"))
      (node (ref "JP2") (pin "5") (pinfunction "5_5") (pintype "passive"))
      (node (ref "R2") (pin "1") (pinfunction "A_1") (pintype "passive"))
      (node (ref "SJ4") (pin "1") (pinfunction "1_1") (pintype "passive"))
    )
    (net (code "87") (name "/USBVBUS") (class "Default")
      (node (ref "C3") (pin "1") (pinfunction "1_1") (pintype "passive"))
      (node (ref "D1") (pin "C") (pinfunction "C_C") (pintype "passive"))
      (node (ref "LM317") (pin "1") (pinfunction "1_1") (pintype "passive"))
      (node (ref "SJ12") (pin "1") (pinfunction "1_1") (pintype "passive"))
      (node (ref "SJ13") (pin "1") (pinfunction "1_1") (pintype "passive"))
      (node (ref "SJ14") (pin "1") (pinfunction "1_1") (pintype "passive"))
      (node (ref "SJ5") (pin "1") (pinfunction "1_1") (pintype "passive"))
      (node (ref "SJ6") (pin "1") (pinfunction "1_1") (pintype "passive"))
      (node (ref "SJ8") (pin "2") (pinfunction "2_2") (pintype "passive"))
      (node (ref "SJ9") (pin "2") (pinfunction "2_2") (pintype "passive"))
    )
    (net (code "88") (name "/V3.3") (class "Default")
      (node (ref "C1") (pin "1") (pinfunction "1_1") (pintype "passive"))
      (node (ref "C10") (pin "1") (pinfunction "1_1") (pintype "passive"))
      (node (ref "C11") (pin "1") (pinfunction "1_1") (pintype "passive"))
      (node (ref "C14") (pin "1") (pinfunction "1_1") (pintype "passive"))
      (node (ref "C15") (pin "1") (pinfunction "1_1") (pintype "passive"))
      (node (ref "C16") (pin "1") (pinfunction "1_1") (pintype "passive"))
      (node (ref "C6") (pin "1") (pinfunction "1_1") (pintype "passive"))
      (node (ref "C7") (pin "1") (pinfunction "1_1") (pintype "passive"))
      (node (ref "C8") (pin "1") (pinfunction "1_1") (pintype "passive"))
      (node (ref "JP6") (pin "14") (pinfunction "14_14") (pintype "passive"))
      (node (ref "JP6") (pin "5") (pinfunction "5_5") (pintype "passive"))
      (node (ref "JP7") (pin "1") (pinfunction "1_1") (pintype "passive"))
      (node (ref "JP8") (pin "1") (pinfunction "1_1") (pintype "passive"))
      (node (ref "R11") (pin "1") (pinfunction "1_1") (pintype "passive"))
      (node (ref "SJ10") (pin "2") (pinfunction "2_2") (pintype "passive"))
      (node (ref "SWD1") (pin "1") (pinfunction "1_1") (pintype "passive"))
      (node (ref "U$15") (pin "VOUT") (pinfunction "VO_VOUT") (pintype "output"))
      (node (ref "U$15") (pin "VOUTB") (pinfunction "BODY_VOUTB") (pintype "open_collector"))
      (node (ref "U$21") (pin "VCC") (pinfunction "VCC_VCC") (pintype "power_in"))
      (node (ref "U$22") (pin "VCC") (pinfunction "VCC_VCC") (pintype "power_in"))
      (node (ref "U$23") (pin "1") (pinfunction "1:VBAT_1") (pintype "bidirectional"))
      (node (ref "U$23") (pin "13") (pinfunction "13:VDDA_13") (pintype "bidirectional"))
      (node (ref "U$23") (pin "19") (pinfunction "19:VDD_19") (pintype "bidirectional"))
      (node (ref "U$23") (pin "32") (pinfunction "32:VDD_32") (pintype "bidirectional"))
      (node (ref "U$23") (pin "48") (pinfunction "48:VDD_48") (pintype "bidirectional"))
      (node (ref "U$23") (pin "64") (pinfunction "64:VDD_64") (pintype "bidirectional"))
      (node (ref "U$24") (pin "V3.3") (pinfunction "V3.3_V3.3") (pintype "bidirectional"))
      (node (ref "U$24") (pin "V3.3@1") (pinfunction "V3.3_V3.3@1") (pintype "bidirectional"))
      (node (ref "U$24") (pin "V3.3@2") (pinfunction "V3.3_V3.3@2") (pintype "bidirectional"))
      (node (ref "U1") (pin "23") (pinfunction "VCCB_2_23") (pintype "power_in"))
      (node (ref "U1") (pin "24") (pinfunction "VCCB_24") (pintype "power_in"))
    )
    (net (code "89") (name "/V5") (class "Default")
      (node (ref "C5") (pin "1") (pinfunction "1_1") (pintype "passive"))
      (node (ref "C9") (pin "1") (pinfunction "1_1") (pintype "passive"))
      (node (ref "JP6") (pin "20") (pinfunction "20_20") (pintype "passive"))
      (node (ref "JP6") (pin "21") (pinfunction "21_21") (pintype "passive"))
      (node (ref "JP6") (pin "30") (pinfunction "30_30") (pintype "passive"))
      (node (ref "JP7") (pin "9") (pinfunction "9_9") (pintype "passive"))
      (node (ref "JP8") (pin "9") (pinfunction "9_9") (pintype "passive"))
      (node (ref "SJ11") (pin "2") (pinfunction "2_2") (pintype "passive"))
      (node (ref "U$13") (pin "16") (pinfunction "VCC1_16") (pintype "bidirectional"))
      (node (ref "U$15") (pin "VIN") (pinfunction "VI_VIN") (pintype "input"))
      (node (ref "U$16") (pin "VO") (pinfunction "P$3_VO") (pintype "output"))
      (node (ref "U$24") (pin "V5") (pinfunction "V5_V5") (pintype "bidirectional"))
      (node (ref "U1") (pin "1") (pinfunction "VCCA_1") (pintype "power_in"))
    )
    (net (code "90") (name "/V12") (class "Default")
      (node (ref "C2") (pin "1") (pinfunction "1_1") (pintype "passive"))
      (node (ref "J2") (pin "3") (pinfunction "3_3") (pintype "passive"))
      (node (ref "SJ3") (pin "2") (pinfunction "2_2") (pintype "passive"))
      (node (ref "U$13") (pin "8") (pinfunction "VCC2_8") (pintype "bidirectional"))
      (node (ref "U$16") (pin "VI") (pinfunction "P$1_VI") (pintype "input"))
    )
    (net (code "91") (name "/VADJ") (class "Default")
      (node (ref "C4") (pin "1") (pinfunction "1_1") (pintype "passive"))
      (node (ref "D2") (pin "A") (pinfunction "A_A") (pintype "passive"))
      (node (ref "LM317") (pin "2") (pinfunction "2_2") (pintype "passive"))
      (node (ref "R1") (pin "1") (pinfunction "1_1") (pintype "passive"))
      (node (ref "R2") (pin "2") (pinfunction "S_2") (pintype "passive"))
    )
    (net (code "92") (name "/VBUS") (class "Default")
      (node (ref "JP2") (pin "2") (pinfunction "2_2") (pintype "passive"))
      (node (ref "JP2") (pin "4") (pinfunction "4_4") (pintype "passive"))
      (node (ref "SJ12") (pin "2") (pinfunction "2_2") (pintype "passive"))
    )
    (net (code "93") (name "/VBUS_A") (class "Default")
      (node (ref "JP1") (pin "4") (pinfunction "4_4") (pintype "passive"))
      (node (ref "SJ14") (pin "2") (pinfunction "2_2") (pintype "passive"))
    )
    (net (code "94") (name "/VCAP") (class "Default")
      (node (ref "C12") (pin "1") (pinfunction "1_1") (pintype "passive"))
      (node (ref "U$23") (pin "30") (pinfunction "30:VCAP_30") (pintype "bidirectional"))
    )
    (net (code "95") (name "/VCONN") (class "Default")
      (node (ref "JP2") (pin "6") (pinfunction "6_6") (pintype "passive"))
      (node (ref "SJ13") (pin "2") (pinfunction "2_2") (pintype "passive"))
    )
    (net (code "96") (name "/VCONNA") (class "Default")
      (node (ref "JP1") (pin "1") (pinfunction "1_1") (pintype "passive"))
      (node (ref "SJ9") (pin "1") (pinfunction "1_1") (pintype "passive"))
    )
    (net (code "97") (name "/VDD") (class "Default")
      (node (ref "JP1") (pin "12") (pinfunction "12_12") (pintype "passive"))
      (node (ref "SJ8") (pin "1") (pinfunction "1_1") (pintype "passive"))
    )
    (net (code "98") (name "/VLT_DIR") (class "Default")
      (node (ref "U$23") (pin "36") (pinfunction "PB15_36") (pintype "bidirectional"))
      (node (ref "U1") (pin "2") (pinfunction "DIR_2") (pintype "input"))
    )
    (net (code "99") (name "/VPU") (class "Default")
      (node (ref "JP1") (pin "11") (pinfunction "11_11") (pintype "passive"))
    )
    (net (code "100") (name "/V_PULLUP") (class "Default")
      (node (ref "JP1") (pin "2") (pinfunction "2_2") (pintype "passive"))
    )
    (net (code "101") (name "/WIFI_CS") (class "Default")
      (node (ref "U$23") (pin "28") (pinfunction "PB2_28") (pintype "bidirectional"))
      (node (ref "U$24") (pin "D8") (pinfunction "D8_D8") (pintype "bidirectional"))
    )
    (net (code "102") (name "/WIFI_GPIO") (class "Default")
      (node (ref "U$24") (pin "D1") (pinfunction "D1_D1") (pintype "bidirectional"))
    )
    (net (code "103") (name "/WIFI_IRQ") (class "Default")
      (node (ref "U$23") (pin "29") (pinfunction "PB10_29") (pintype "bidirectional"))
      (node (ref "U$24") (pin "D0") (pinfunction "D0_D0") (pintype "bidirectional"))
    )
    (net (code "104") (name "Net-(R4-Pad1)") (class "Default")
      (node (ref "R4") (pin "1") (pinfunction "1_1") (pintype "passive"))
      (node (ref "R5") (pin "2") (pinfunction "2_2") (pintype "passive"))
      (node (ref "U$18") (pin "E") (pinfunction "E_E") (pintype "bidirectional"))
    )
    (net (code "105") (name "Net-(R6-Pad1)") (class "Default")
      (node (ref "R6") (pin "1") (pinfunction "1_1") (pintype "passive"))
      (node (ref "U$19") (pin "D") (pinfunction "D_D") (pintype "bidirectional"))
    )
    (net (code "106") (name "Net-(R6-Pad2)") (class "Default")
      (node (ref "R6") (pin "2") (pinfunction "2_2") (pintype "passive"))
      (node (ref "U$18") (pin "CATH") (pinfunction "CATH_CATH") (pintype "bidirectional"))
    )
    (net (code "107") (name "Net-(U$2-11)") (class "Default")
      (node (ref "JP6") (pin "15") (pinfunction "15_15") (pintype "passive"))
      (node (ref "U$2") (pin "P$11") (pinfunction "11_P$11") (pintype "passive"))
    )
    (net (code "108") (name "Net-(U$2-22)") (class "Default")
      (node (ref "JP6") (pin "16") (pinfunction "16_16") (pintype "passive"))
      (node (ref "U$2") (pin "P$22") (pinfunction "22_P$22") (pintype "passive"))
    )
    (net (code "109") (name "Net-(U$2-33)") (class "Default")
      (node (ref "JP6") (pin "17") (pinfunction "17_17") (pintype "passive"))
      (node (ref "U$2") (pin "P$33") (pinfunction "33_P$33") (pintype "passive"))
    )
    (net (code "110") (name "Net-(U$2-44)") (class "Default")
      (node (ref "JP6") (pin "18") (pinfunction "18_18") (pintype "passive"))
      (node (ref "U$2") (pin "P$44") (pinfunction "44_P$44") (pintype "passive"))
    )
    (net (code "111") (name "Net-(U$6-11)") (class "Default")
      (node (ref "JP6") (pin "23") (pinfunction "23_23") (pintype "passive"))
      (node (ref "U$6") (pin "P$11") (pinfunction "11_P$11") (pintype "passive"))
    )
    (net (code "112") (name "Net-(U$6-22)") (class "Default")
      (node (ref "JP6") (pin "24") (pinfunction "24_24") (pintype "passive"))
      (node (ref "U$6") (pin "P$22") (pinfunction "22_P$22") (pintype "passive"))
    )
    (net (code "113") (name "Net-(U$6-33)") (class "Default")
      (node (ref "JP6") (pin "26") (pinfunction "26_26") (pintype "passive"))
      (node (ref "U$6") (pin "P$33") (pinfunction "33_P$33") (pintype "passive"))
    )
    (net (code "114") (name "Net-(U$7-11)") (class "Default")
      (node (ref "JP6") (pin "25") (pinfunction "25_25") (pintype "passive"))
      (node (ref "U$7") (pin "P$11") (pinfunction "11_P$11") (pintype "passive"))
    )
    (net (code "115") (name "Net-(U$7-22)") (class "Default")
      (node (ref "JP6") (pin "28") (pinfunction "28_28") (pintype "passive"))
      (node (ref "U$7") (pin "P$22") (pinfunction "22_P$22") (pintype "passive"))
    )
    (net (code "116") (name "Net-(U$7-33)") (class "Default")
      (node (ref "JP6") (pin "27") (pinfunction "27_27") (pintype "passive"))
      (node (ref "U$7") (pin "P$33") (pinfunction "33_P$33") (pintype "passive"))
    )
    (net (code "117") (name "Net-(U$8-11)") (class "Default")
      (node (ref "JP8") (pin "5") (pinfunction "5_5") (pintype "passive"))
      (node (ref "U$8") (pin "P$11") (pinfunction "11_P$11") (pintype "passive"))
    )
    (net (code "118") (name "Net-(U$8-22)") (class "Default")
      (node (ref "JP8") (pin "4") (pinfunction "4_4") (pintype "passive"))
      (node (ref "U$8") (pin "P$22") (pinfunction "22_P$22") (pintype "passive"))
    )
    (net (code "119") (name "Net-(U$8-33)") (class "Default")
      (node (ref "JP8") (pin "3") (pinfunction "3_3") (pintype "passive"))
      (node (ref "U$8") (pin "P$33") (pinfunction "33_P$33") (pintype "passive"))
    )
    (net (code "120") (name "Net-(U$8-44)") (class "Default")
      (node (ref "JP8") (pin "2") (pinfunction "2_2") (pintype "passive"))
      (node (ref "U$8") (pin "P$44") (pinfunction "44_P$44") (pintype "passive"))
    )
    (net (code "121") (name "Net-(U$9-11)") (class "Default")
      (node (ref "JP7") (pin "5") (pinfunction "5_5") (pintype "passive"))
      (node (ref "U$9") (pin "P$11") (pinfunction "11_P$11") (pintype "passive"))
    )
    (net (code "122") (name "Net-(U$9-22)") (class "Default")
      (node (ref "JP7") (pin "4") (pinfunction "4_4") (pintype "passive"))
      (node (ref "U$9") (pin "P$22") (pinfunction "22_P$22") (pintype "passive"))
    )
    (net (code "123") (name "Net-(U$9-33)") (class "Default")
      (node (ref "JP7") (pin "3") (pinfunction "3_3") (pintype "passive"))
      (node (ref "U$9") (pin "P$33") (pinfunction "33_P$33") (pintype "passive"))
    )
    (net (code "124") (name "Net-(U$9-44)") (class "Default")
      (node (ref "JP7") (pin "2") (pinfunction "2_2") (pintype "passive"))
      (node (ref "U$9") (pin "P$44") (pinfunction "44_P$44") (pintype "passive"))
    )
    (net (code "125") (name "Net-(U$10-33)") (class "Default")
      (node (ref "JP7") (pin "7") (pinfunction "7_7") (pintype "passive"))
      (node (ref "U$10") (pin "P$33") (pinfunction "33_P$33") (pintype "passive"))
    )
    (net (code "126") (name "Net-(U$10-44)") (class "Default")
      (node (ref "JP7") (pin "6") (pinfunction "6_6") (pintype "passive"))
      (node (ref "U$10") (pin "P$44") (pinfunction "44_P$44") (pintype "passive"))
    )
    (net (code "127") (name "Net-(U$11-33)") (class "Default")
      (node (ref "JP8") (pin "7") (pinfunction "7_7") (pintype "passive"))
      (node (ref "U$11") (pin "P$33") (pinfunction "33_P$33") (pintype "passive"))
    )
    (net (code "128") (name "Net-(U$11-44)") (class "Default")
      (node (ref "JP8") (pin "6") (pinfunction "6_6") (pintype "passive"))
      (node (ref "U$11") (pin "P$44") (pinfunction "44_P$44") (pintype "passive"))
    )
    (net (code "129") (name "Net-(U$23-PH1)") (class "Default")
      (node (ref "R3") (pin "2") (pinfunction "2_2") (pintype "passive"))
      (node (ref "U$23") (pin "6") (pinfunction "PH1_6") (pintype "bidirectional"))
    )
    (net (code "130") (name "unconnected-(JP1-Pad3)") (class "Default")
      (node (ref "JP1") (pin "3") (pinfunction "3_3") (pintype "passive"))
    )
    (net (code "131") (name "unconnected-(JP6-Pad29)") (class "Default")
      (node (ref "JP6") (pin "29") (pinfunction "29_29") (pintype "passive"))
    )
    (net (code "132") (name "unconnected-(R2-E-Pad3)") (class "Default")
      (node (ref "R2") (pin "3") (pinfunction "E_3") (pintype "passive"))
    )
    (net (code "133") (name "unconnected-(U$4-4-PadP$4)") (class "Default")
      (node (ref "U$4") (pin "P$4") (pinfunction "4_P$4") (pintype "passive"))
    )
    (net (code "134") (name "unconnected-(U$4-44-PadP$44)") (class "Default")
      (node (ref "U$4") (pin "P$44") (pinfunction "44_P$44") (pintype "passive"))
    )
    (net (code "135") (name "unconnected-(U$6-4-PadP$4)") (class "Default")
      (node (ref "U$6") (pin "P$4") (pinfunction "4_P$4") (pintype "passive"))
    )
    (net (code "136") (name "unconnected-(U$6-44-PadP$44)") (class "Default")
      (node (ref "U$6") (pin "P$44") (pinfunction "44_P$44") (pintype "passive"))
    )
    (net (code "137") (name "unconnected-(U$7-4-PadP$4)") (class "Default")
      (node (ref "U$7") (pin "P$4") (pinfunction "4_P$4") (pintype "passive"))
    )
    (net (code "138") (name "unconnected-(U$7-44-PadP$44)") (class "Default")
      (node (ref "U$7") (pin "P$44") (pinfunction "44_P$44") (pintype "passive"))
    )
    (net (code "139") (name "unconnected-(U$10-1-PadP$1)") (class "Default")
      (node (ref "U$10") (pin "P$1") (pinfunction "1_P$1") (pintype "passive"))
    )
    (net (code "140") (name "unconnected-(U$10-2-PadP$2)") (class "Default")
      (node (ref "U$10") (pin "P$2") (pinfunction "2_P$2") (pintype "passive"))
    )
    (net (code "141") (name "unconnected-(U$10-11-PadP$11)") (class "Default")
      (node (ref "U$10") (pin "P$11") (pinfunction "11_P$11") (pintype "passive"))
    )
    (net (code "142") (name "unconnected-(U$10-22-PadP$22)") (class "Default")
      (node (ref "U$10") (pin "P$22") (pinfunction "22_P$22") (pintype "passive"))
    )
    (net (code "143") (name "unconnected-(U$11-1-PadP$1)") (class "Default")
      (node (ref "U$11") (pin "P$1") (pinfunction "1_P$1") (pintype "passive"))
    )
    (net (code "144") (name "unconnected-(U$11-2-PadP$2)") (class "Default")
      (node (ref "U$11") (pin "P$2") (pinfunction "2_P$2") (pintype "passive"))
    )
    (net (code "145") (name "unconnected-(U$11-11-PadP$11)") (class "Default")
      (node (ref "U$11") (pin "P$11") (pinfunction "11_P$11") (pintype "passive"))
    )
    (net (code "146") (name "unconnected-(U$11-22-PadP$22)") (class "Default")
      (node (ref "U$11") (pin "P$22") (pinfunction "22_P$22") (pintype "passive"))
    )
    (net (code "147") (name "unconnected-(U$24-PadA0)") (class "Default")
      (node (ref "U$24") (pin "A0") (pinfunction "A0_A0") (pintype "bidirectional"))
    )
    (net (code "148") (name "unconnected-(U$24-PadCLK)") (class "Default")
      (node (ref "U$24") (pin "CLK") (pinfunction "CLK_CLK") (pintype "bidirectional"))
    )
    (net (code "149") (name "unconnected-(U$24-PadCMD)") (class "Default")
      (node (ref "U$24") (pin "CMD") (pinfunction "CMD_CMD") (pintype "bidirectional"))
    )
    (net (code "150") (name "unconnected-(U$24-PadD2)") (class "Default")
      (node (ref "U$24") (pin "D2") (pinfunction "D2_D2") (pintype "bidirectional"))
    )
    (net (code "151") (name "unconnected-(U$24-PadD3)") (class "Default")
      (node (ref "U$24") (pin "D3") (pinfunction "D3_D3") (pintype "bidirectional"))
    )
    (net (code "152") (name "unconnected-(U$24-PadD4)") (class "Default")
      (node (ref "U$24") (pin "D4") (pinfunction "D4_D4") (pintype "bidirectional"))
    )
    (net (code "153") (name "unconnected-(U$24-PadEN)") (class "Default")
      (node (ref "U$24") (pin "EN") (pinfunction "EN_EN") (pintype "bidirectional"))
    )
    (net (code "154") (name "unconnected-(U$24-PadRST)") (class "Default")
      (node (ref "U$24") (pin "RST") (pinfunction "RST_RST") (pintype "bidirectional"))
    )
    (net (code "155") (name "unconnected-(U$24-PadRSV)") (class "Default")
      (node (ref "U$24") (pin "RSV") (pinfunction "RSV_RSV") (pintype "bidirectional"))
    )
    (net (code "156") (name "unconnected-(U$24-PadRX)") (class "Default")
      (node (ref "U$24") (pin "RX") (pinfunction "RX_RX") (pintype "bidirectional"))
    )
    (net (code "157") (name "unconnected-(U$24-PadSD0)") (class "Default")
      (node (ref "U$24") (pin "SD0") (pinfunction "SD0_SD0") (pintype "bidirectional"))
    )
    (net (code "158") (name "unconnected-(U$24-PadSD1)") (class "Default")
      (node (ref "U$24") (pin "SD1") (pinfunction "SD1_SD1") (pintype "bidirectional"))
    )
    (net (code "159") (name "unconnected-(U$24-PadSD2)") (class "Default")
      (node (ref "U$24") (pin "SD2") (pinfunction "SD2_SD2") (pintype "bidirectional"))
    )
    (net (code "160") (name "unconnected-(U$24-PadSD3)") (class "Default")
      (node (ref "U$24") (pin "SD3") (pinfunction "SD3_SD3") (pintype "bidirectional"))
    )
    (net (code "161") (name "unconnected-(U$24-PadTX)") (class "Default")
      (node (ref "U$24") (pin "TX") (pinfunction "TX_TX") (pintype "bidirectional"))
    )
    (net (code "162") (name "unconnected-(U$24-RSV-PadRSV@1)") (class "Default")
      (node (ref "U$24") (pin "RSV@1") (pinfunction "RSV_RSV@1") (pintype "bidirectional"))
    )
    (net (code "163") (name "unconnected-(U1-A6-Pad9)") (class "Default")
      (node (ref "U1") (pin "9") (pinfunction "A6_9") (pintype "bidirectional"))
    )
    (net (code "164") (name "unconnected-(U1-A7-Pad10)") (class "Default")
      (node (ref "U1") (pin "10") (pinfunction "A7_10") (pintype "bidirectional"))
    )
    (net (code "165") (name "unconnected-(U1-B6-Pad15)") (class "Default")
      (node (ref "U1") (pin "15") (pinfunction "B6_15") (pintype "bidirectional"))
    )
    (net (code "166") (name "unconnected-(U1-B7-Pad14)") (class "Default")
      (node (ref "U1") (pin "14") (pinfunction "B7_14") (pintype "bidirectional"))
    )
  )
)
